# gpio4s2.net
KiCad netlist of a schematic drawn in EAGLE
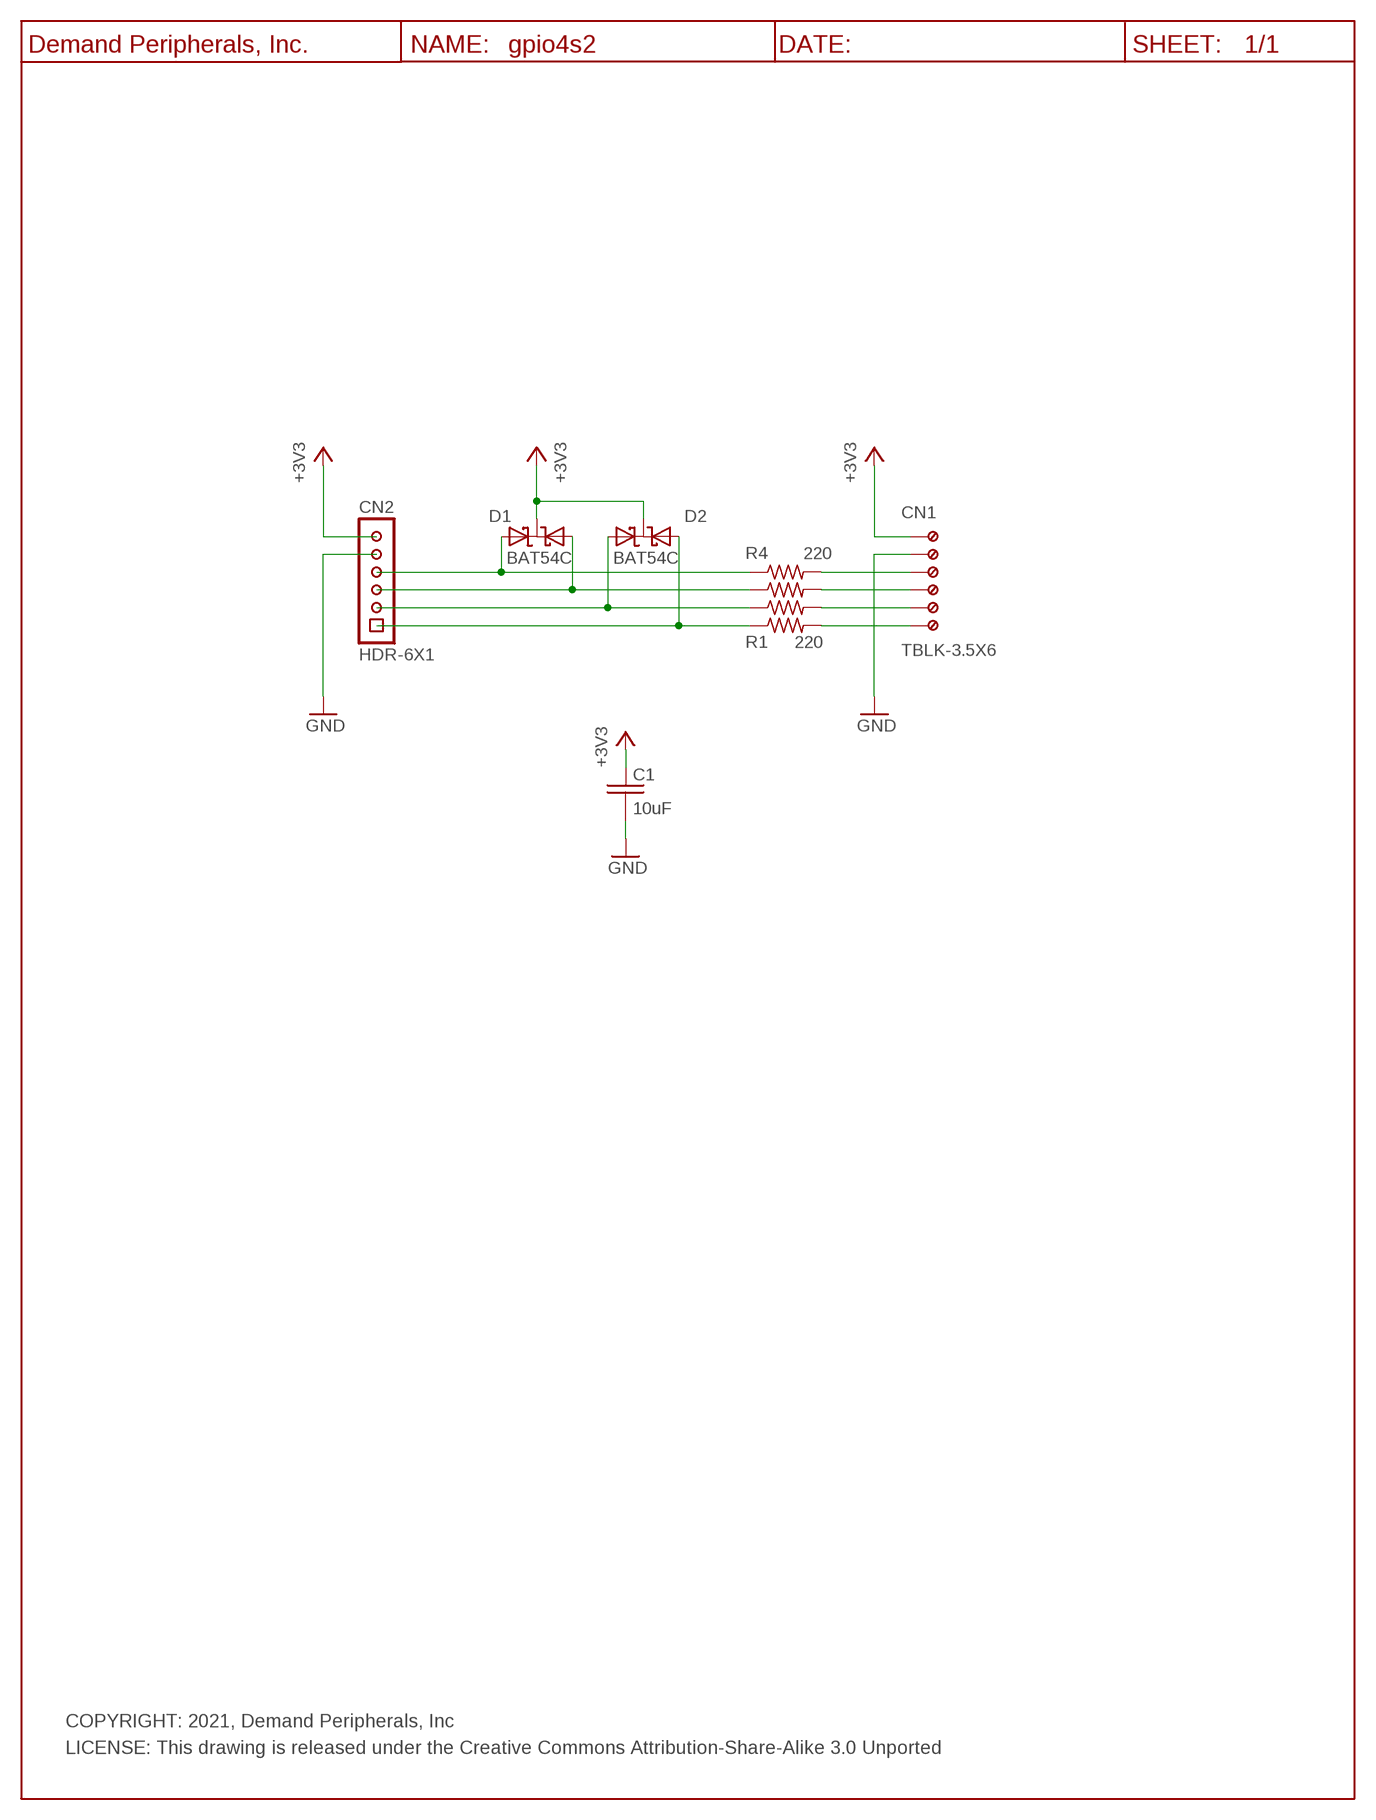
[diagram p0: schematic, sheet 1]

(export (version "E")
  (design (tool "Eeschema 10.0.6"))
  (components
    (comp (ref "C1")
      (value "10uF")
      (footprint "eagle-import:C1206")
      (libsource (lib "eagle-import") (part "C10UF25V_C1206"))
    )
    (comp (ref "CN1")
      (value "TBLK-3.5X6")
      (footprint "eagle-import:TBLK-3.5X6")
      (libsource (lib "eagle-import") (part "TBLK-3.5X6"))
    )
    (comp (ref "CN2")
      (value "HDR-6X1")
      (footprint "eagle-import:HDR-6X1")
      (libsource (lib "eagle-import") (part "HDR-6X1"))
    )
    (comp (ref "D1")
      (value "BAT54C")
      (footprint "eagle-import:SOT23")
      (libsource (lib "eagle-import") (part "BAT54C"))
    )
    (comp (ref "D2")
      (value "BAT54C")
      (footprint "eagle-import:SOT23")
      (libsource (lib "eagle-import") (part "BAT54C"))
    )
    (comp (ref "R1")
      (value "220")
      (footprint "eagle-import:R0603")
      (libsource (lib "eagle-import") (part "R220_R0603"))
    )
    (comp (ref "R2")
      (value "220")
      (footprint "eagle-import:R0603")
      (libsource (lib "eagle-import") (part "R220_R0603"))
    )
    (comp (ref "R3")
      (value "220")
      (footprint "eagle-import:R0603")
      (libsource (lib "eagle-import") (part "R220_R0603"))
    )
    (comp (ref "R4")
      (value "220")
      (footprint "eagle-import:R0603")
      (libsource (lib "eagle-import") (part "R220_R0603"))
    )
    (comp (ref "U$1")
      (value "DP_FRAME_P")
      (footprint "eagle-import:P_FRAME")
      (libsource (lib "eagle-import") (part "DP_FRAME_P"))
    )
  )
  (nets
    (net (code "1") (name "+3V3") (class "Default")
      (node (ref "C1") (pin "1") (pinfunction "1_1") (pintype "passive"))
      (node (ref "CN1") (pin "1") (pinfunction "KL_1") (pintype "passive"))
      (node (ref "CN2") (pin "6") (pinfunction "6_6") (pintype "passive"))
      (node (ref "D1") (pin "3") (pinfunction "CC_3") (pintype "passive"))
      (node (ref "D2") (pin "3") (pinfunction "CC_3") (pintype "passive"))
    )
    (net (code "2") (name "GND") (class "Default")
      (node (ref "C1") (pin "2") (pinfunction "2_2") (pintype "passive"))
      (node (ref "CN1") (pin "2") (pinfunction "KL1_2") (pintype "passive"))
      (node (ref "CN2") (pin "5") (pinfunction "5_5") (pintype "passive"))
    )
    (net (code "3") (name "Net-(CN1-KL2)") (class "Default")
      (node (ref "CN1") (pin "3") (pinfunction "KL2_3") (pintype "passive"))
      (node (ref "R4") (pin "2") (pinfunction "2_2") (pintype "passive"))
    )
    (net (code "4") (name "Net-(CN1-KL3)") (class "Default")
      (node (ref "CN1") (pin "4") (pinfunction "KL3_4") (pintype "passive"))
      (node (ref "R3") (pin "2") (pinfunction "2_2") (pintype "passive"))
    )
    (net (code "5") (name "Net-(CN1-KL4)") (class "Default")
      (node (ref "CN1") (pin "5") (pinfunction "KL4_5") (pintype "passive"))
      (node (ref "R2") (pin "2") (pinfunction "2_2") (pintype "passive"))
    )
    (net (code "6") (name "Net-(CN1-KL5)") (class "Default")
      (node (ref "CN1") (pin "6") (pinfunction "KL5_6") (pintype "passive"))
      (node (ref "R1") (pin "2") (pinfunction "2_2") (pintype "passive"))
    )
    (net (code "7") (name "Net-(D1-A)") (class "Default")
      (node (ref "CN2") (pin "3") (pinfunction "3_3") (pintype "passive"))
      (node (ref "D1") (pin "2") (pinfunction "A_2") (pintype "passive"))
      (node (ref "R3") (pin "1") (pinfunction "1_1") (pintype "passive"))
    )
    (net (code "8") (name "Net-(D1-A1)") (class "Default")
      (node (ref "CN2") (pin "4") (pinfunction "4_4") (pintype "passive"))
      (node (ref "D1") (pin "1") (pinfunction "A1_1") (pintype "passive"))
      (node (ref "R4") (pin "1") (pinfunction "1_1") (pintype "passive"))
    )
    (net (code "9") (name "Net-(D2-A)") (class "Default")
      (node (ref "CN2") (pin "1") (pinfunction "1_1") (pintype "passive"))
      (node (ref "D2") (pin "2") (pinfunction "A_2") (pintype "passive"))
      (node (ref "R1") (pin "1") (pinfunction "1_1") (pintype "passive"))
    )
    (net (code "10") (name "Net-(D2-A1)") (class "Default")
      (node (ref "CN2") (pin "2") (pinfunction "2_2") (pintype "passive"))
      (node (ref "D2") (pin "1") (pinfunction "A1_1") (pintype "passive"))
      (node (ref "R2") (pin "1") (pinfunction "1_1") (pintype "passive"))
    )
  )
)
